# placa_sensor3.net
KiCad netlist of a schematic drawn in EAGLE
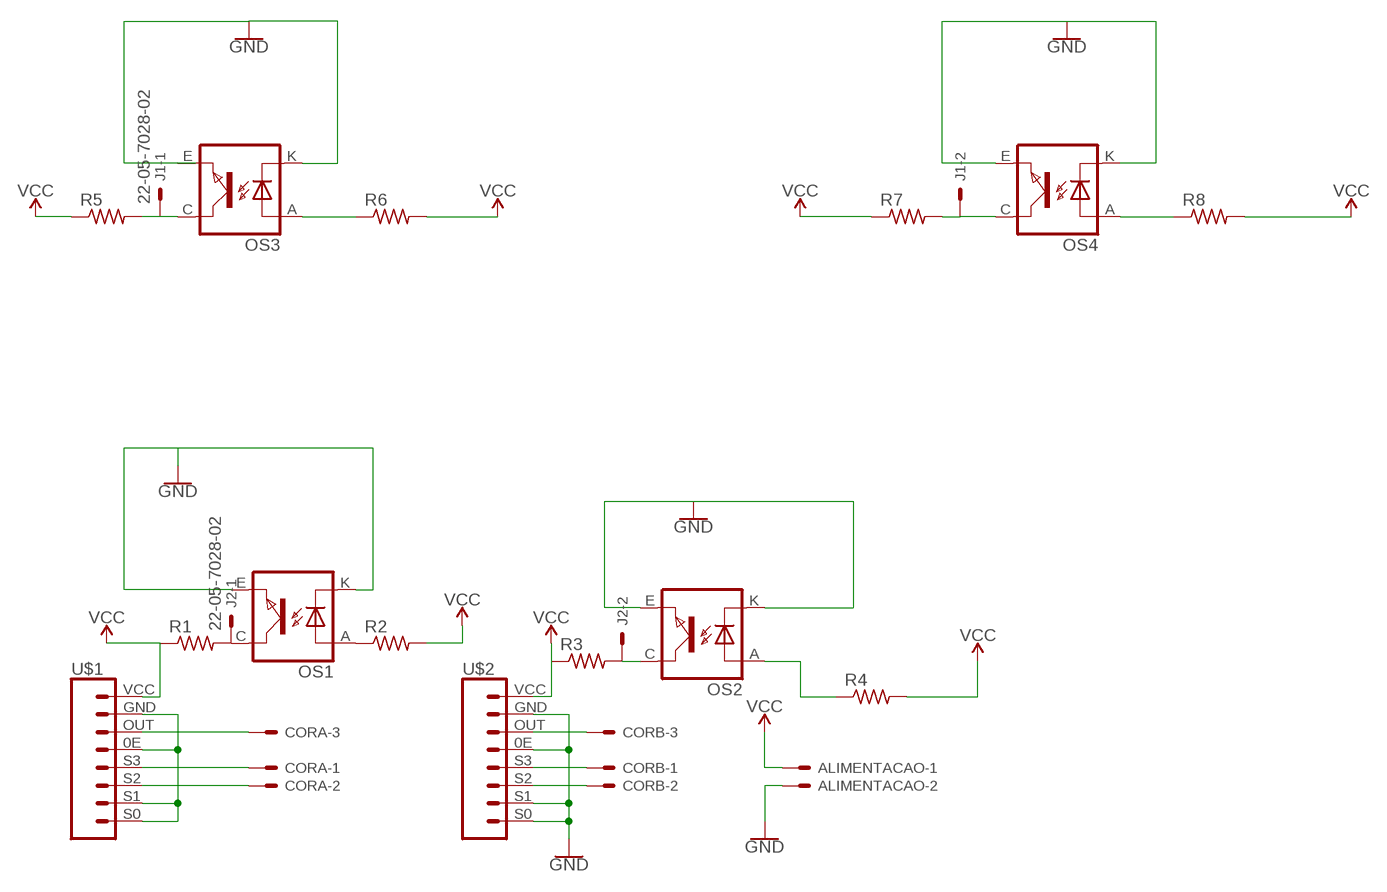
[diagram p0: schematic, sheet 1]

(export (version "E")
  (design (tool "Eeschema 10.0.6"))
  (components
    (comp (ref "ALIMENTACAO")
      (value "22-05-7028-02")
      (footprint "eagle-import:7395-02")
      (libsource (lib "eagle-import") (part "22-?-0205-7028"))
    )
    (comp (ref "CORA")
      (value "22-05-7038-03")
      (footprint "eagle-import:7395-03")
      (libsource (lib "eagle-import") (part "22-?-0305-7038"))
    )
    (comp (ref "CORB")
      (value "22-05-7038-03")
      (footprint "eagle-import:7395-03")
      (libsource (lib "eagle-import") (part "22-?-0305-7038"))
    )
    (comp (ref "J1")
      (value "22-05-7028-02")
      (footprint "eagle-import:7395-02")
      (libsource (lib "eagle-import") (part "22-?-0205-7028"))
    )
    (comp (ref "J2")
      (value "22-05-7028-02")
      (footprint "eagle-import:7395-02")
      (libsource (lib "eagle-import") (part "22-?-0205-7028"))
    )
    (comp (ref "OS1")
      (value "TCRT5000")
      (footprint "eagle-import:TCRT5000")
      (libsource (lib "eagle-import") (part "TCRT5000"))
    )
    (comp (ref "OS2")
      (value "TCRT5000")
      (footprint "eagle-import:TCRT5000")
      (libsource (lib "eagle-import") (part "TCRT5000"))
    )
    (comp (ref "OS3")
      (value "TCRT5000")
      (footprint "eagle-import:TCRT5000")
      (libsource (lib "eagle-import") (part "TCRT5000"))
    )
    (comp (ref "OS4")
      (value "TCRT5000")
      (footprint "eagle-import:TCRT5000")
      (libsource (lib "eagle-import") (part "TCRT5000"))
    )
    (comp (ref "R1")
      (value "R-US_0204/5")
      (footprint "eagle-import:0204_5")
      (libsource (lib "eagle-import") (part "R-US_0204/5"))
    )
    (comp (ref "R2")
      (value "R-US_0204/5")
      (footprint "eagle-import:0204_5")
      (libsource (lib "eagle-import") (part "R-US_0204/5"))
    )
    (comp (ref "R3")
      (value "R-US_0204/5")
      (footprint "eagle-import:0204_5")
      (libsource (lib "eagle-import") (part "R-US_0204/5"))
    )
    (comp (ref "R4")
      (value "R-US_0204/5")
      (footprint "eagle-import:0204_5")
      (libsource (lib "eagle-import") (part "R-US_0204/5"))
    )
    (comp (ref "R5")
      (value "R-US_0204/5")
      (footprint "eagle-import:0204_5")
      (libsource (lib "eagle-import") (part "R-US_0204/5"))
    )
    (comp (ref "R6")
      (value "R-US_0204/5")
      (footprint "eagle-import:0204_5")
      (libsource (lib "eagle-import") (part "R-US_0204/5"))
    )
    (comp (ref "R7")
      (value "R-US_0204/5")
      (footprint "eagle-import:0204_5")
      (libsource (lib "eagle-import") (part "R-US_0204/5"))
    )
    (comp (ref "R8")
      (value "R-US_0204/5")
      (footprint "eagle-import:0204_5")
      (libsource (lib "eagle-import") (part "R-US_0204/5"))
    )
    (comp (ref "U$1")
      (value "TCS3200_2TCS3200_2")
      (footprint "eagle-import:TCS3200_2")
      (libsource (lib "eagle-import") (part "TCS3200_2TCS3200_2"))
    )
    (comp (ref "U$2")
      (value "TCS3200_2TCS3200_2")
      (footprint "eagle-import:TCS3200_2")
      (libsource (lib "eagle-import") (part "TCS3200_2TCS3200_2"))
    )
  )
  (nets
    (net (code "1") (name "GND") (class "Default")
      (node (ref "ALIMENTACAO") (pin "2") (pinfunction "S_2") (pintype "passive"))
      (node (ref "OS1") (pin "E") (pinfunction "EMITTER_E") (pintype "passive"))
      (node (ref "OS1") (pin "K") (pinfunction "CATHODE_K") (pintype "passive"))
      (node (ref "OS2") (pin "E") (pinfunction "EMITTER_E") (pintype "passive"))
      (node (ref "OS2") (pin "K") (pinfunction "CATHODE_K") (pintype "passive"))
      (node (ref "OS3") (pin "K") (pinfunction "CATHODE_K") (pintype "passive"))
      (node (ref "OS4") (pin "E") (pinfunction "EMITTER_E") (pintype "passive"))
      (node (ref "OS4") (pin "K") (pinfunction "CATHODE_K") (pintype "passive"))
      (node (ref "U$2") (pin "0E") (pinfunction "0E_0E") (pintype "passive"))
      (node (ref "U$2") (pin "GND") (pinfunction "GND_GND") (pintype "passive"))
      (node (ref "U$2") (pin "S0") (pinfunction "S0_S0") (pintype "passive"))
      (node (ref "U$2") (pin "S1") (pinfunction "S1_S1") (pintype "passive"))
    )
    (net (code "2") (name "Net-(CORAA-S)") (class "Default")
      (node (ref "CORA") (pin "1") (pinfunction "S_1") (pintype "passive"))
      (node (ref "U$1") (pin "S3") (pinfunction "S3_S3") (pintype "passive"))
    )
    (net (code "3") (name "Net-(CORAB-S)") (class "Default")
      (node (ref "CORA") (pin "2") (pinfunction "S_2") (pintype "passive"))
      (node (ref "U$1") (pin "S2") (pinfunction "S2_S2") (pintype "passive"))
    )
    (net (code "4") (name "Net-(CORAC-S)") (class "Default")
      (node (ref "CORA") (pin "3") (pinfunction "S_3") (pintype "passive"))
      (node (ref "U$1") (pin "OUT") (pinfunction "OUT_OUT") (pintype "passive"))
    )
    (net (code "5") (name "Net-(CORBA-S)") (class "Default")
      (node (ref "CORB") (pin "1") (pinfunction "S_1") (pintype "passive"))
      (node (ref "U$2") (pin "S3") (pinfunction "S3_S3") (pintype "passive"))
    )
    (net (code "6") (name "Net-(CORBB-S)") (class "Default")
      (node (ref "CORB") (pin "2") (pinfunction "S_2") (pintype "passive"))
      (node (ref "U$2") (pin "S2") (pinfunction "S2_S2") (pintype "passive"))
    )
    (net (code "7") (name "Net-(CORBC-S)") (class "Default")
      (node (ref "CORB") (pin "3") (pinfunction "S_3") (pintype "passive"))
      (node (ref "U$2") (pin "OUT") (pinfunction "OUT_OUT") (pintype "passive"))
    )
    (net (code "8") (name "Net-(J1A-S)") (class "Default")
      (node (ref "J1") (pin "1") (pinfunction "S_1") (pintype "passive"))
      (node (ref "OS3") (pin "C") (pinfunction "COLLECTOR_C") (pintype "passive"))
      (node (ref "R5") (pin "2") (pinfunction "2_2") (pintype "passive"))
    )
    (net (code "9") (name "Net-(J1B-S)") (class "Default")
      (node (ref "J1") (pin "2") (pinfunction "S_2") (pintype "passive"))
      (node (ref "OS4") (pin "C") (pinfunction "COLLECTOR_C") (pintype "passive"))
      (node (ref "R7") (pin "2") (pinfunction "2_2") (pintype "passive"))
    )
    (net (code "10") (name "Net-(J2A-S)") (class "Default")
      (node (ref "J2") (pin "1") (pinfunction "S_1") (pintype "passive"))
      (node (ref "OS1") (pin "C") (pinfunction "COLLECTOR_C") (pintype "passive"))
      (node (ref "R1") (pin "2") (pinfunction "2_2") (pintype "passive"))
    )
    (net (code "11") (name "Net-(J2B-S)") (class "Default")
      (node (ref "J2") (pin "2") (pinfunction "S_2") (pintype "passive"))
      (node (ref "OS2") (pin "C") (pinfunction "COLLECTOR_C") (pintype "passive"))
      (node (ref "R3") (pin "2") (pinfunction "2_2") (pintype "passive"))
    )
    (net (code "12") (name "Net-(OS1-ANODE)") (class "Default")
      (node (ref "OS1") (pin "A") (pinfunction "ANODE_A") (pintype "passive"))
      (node (ref "R2") (pin "1") (pinfunction "1_1") (pintype "passive"))
    )
    (net (code "13") (name "Net-(OS2-ANODE)") (class "Default")
      (node (ref "OS2") (pin "A") (pinfunction "ANODE_A") (pintype "passive"))
      (node (ref "R4") (pin "1") (pinfunction "1_1") (pintype "passive"))
    )
    (net (code "14") (name "Net-(OS3-ANODE)") (class "Default")
      (node (ref "OS3") (pin "A") (pinfunction "ANODE_A") (pintype "passive"))
      (node (ref "R6") (pin "1") (pinfunction "1_1") (pintype "passive"))
    )
    (net (code "15") (name "Net-(OS4-ANODE)") (class "Default")
      (node (ref "OS4") (pin "A") (pinfunction "ANODE_A") (pintype "passive"))
      (node (ref "R8") (pin "1") (pinfunction "1_1") (pintype "passive"))
    )
    (net (code "16") (name "Net-(U$1-Pad0E)") (class "Default")
      (node (ref "U$1") (pin "0E") (pinfunction "0E_0E") (pintype "passive"))
      (node (ref "U$1") (pin "GND") (pinfunction "GND_GND") (pintype "passive"))
      (node (ref "U$1") (pin "S0") (pinfunction "S0_S0") (pintype "passive"))
      (node (ref "U$1") (pin "S1") (pinfunction "S1_S1") (pintype "passive"))
    )
    (net (code "17") (name "VCC") (class "Default")
      (node (ref "ALIMENTACAO") (pin "1") (pinfunction "S_1") (pintype "passive"))
      (node (ref "R1") (pin "1") (pinfunction "1_1") (pintype "passive"))
      (node (ref "R2") (pin "2") (pinfunction "2_2") (pintype "passive"))
      (node (ref "R3") (pin "1") (pinfunction "1_1") (pintype "passive"))
      (node (ref "R4") (pin "2") (pinfunction "2_2") (pintype "passive"))
      (node (ref "R5") (pin "1") (pinfunction "1_1") (pintype "passive"))
      (node (ref "R6") (pin "2") (pinfunction "2_2") (pintype "passive"))
      (node (ref "R7") (pin "1") (pinfunction "1_1") (pintype "passive"))
      (node (ref "R8") (pin "2") (pinfunction "2_2") (pintype "passive"))
      (node (ref "U$1") (pin "VCC") (pinfunction "VCC_VCC") (pintype "passive"))
      (node (ref "U$2") (pin "VCC") (pinfunction "VCC_VCC") (pintype "passive"))
    )
    (net (code "18") (name "unconnected-(OS3-EMITTER-PadE)") (class "Default")
      (node (ref "OS3") (pin "E") (pinfunction "EMITTER_E") (pintype "passive"))
    )
  )
)
